# Redundant_Batteries.net
KiCad netlist of a schematic drawn in Altium Designer
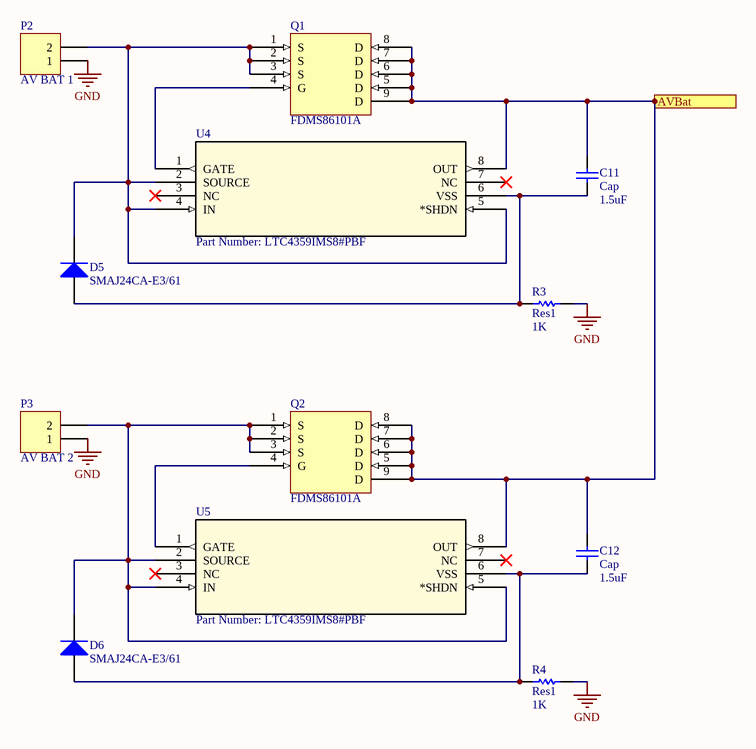
[diagram p0: Redundant Batteries.SchDoc]

(export (version "E")
  (design (tool "Eeschema 10.0.6"))
  (components
    (comp (ref "C11")
      (value "Cap")
      (footprint "CAP_2012")
      (description "Capacitor")
      (fields (field (name "ALTIUM_VALUE") "1.5uF") (field (name "PUBLISHER") "Altium Limited"))
      (libsource (lib "Miscellaneous Devices") (part "Cap"))
    )
    (comp (ref "C12")
      (value "Cap")
      (footprint "CAP_2012")
      (description "Capacitor")
      (fields (field (name "ALTIUM_VALUE") "1.5uF") (field (name "PUBLISHER") "Altium Limited"))
      (libsource (lib "Miscellaneous Devices") (part "Cap"))
    )
    (comp (ref "D5")
      (value "SMAJ24CA-E3/61")
      (footprint "DIODE_DO-214AC")
      (description "Default Diode")
      (fields (field (name "PUBLISHER") "Altium Limited"))
      (libsource (lib "Miscellaneous Devices") (part "Diode"))
    )
    (comp (ref "D6")
      (value "SMAJ24CA-E3/61")
      (footprint "DIODE_DO-214AC")
      (description "Default Diode")
      (fields (field (name "PUBLISHER") "Altium Limited"))
      (libsource (lib "Miscellaneous Devices") (part "Diode"))
    )
    (comp (ref "P2")
      (value "AV BAT 1")
      (footprint "M80-5000000M5-02-333-00-000")
      (description "Header, 2-Pin")
      (fields (field (name "PUBLISHER") "Altium Limited"))
      (libsource (lib "Miscellaneous Connectors") (part "Header 2"))
    )
    (comp (ref "P3")
      (value "AV BAT 2")
      (footprint "M80-5000000M5-02-333-00-000")
      (description "Header, 2-Pin")
      (fields (field (name "PUBLISHER") "Altium Limited"))
      (libsource (lib "Miscellaneous Connectors") (part "Header 2"))
    )
    (comp (ref "Q1")
      (value "FDMS86101A")
      (footprint "FDMS86101A")
      (description "MOSFET N-CH 100V 13A POWER56")
      (libsource (lib "FDMS86101A") (part "FDMS86101A"))
    )
    (comp (ref "Q2")
      (value "FDMS86101A")
      (footprint "FDMS86101A")
      (description "MOSFET N-CH 100V 13A POWER56")
      (libsource (lib "FDMS86101A") (part "FDMS86101A"))
    )
    (comp (ref "R3")
      (value "Res1")
      (footprint "STA_RMCF2512")
      (description "Resistor")
      (fields (field (name "ALTIUM_VALUE") "1K") (field (name "PUBLISHER") "Altium Limited"))
      (libsource (lib "Miscellaneous Devices") (part "Res1"))
    )
    (comp (ref "R4")
      (value "Res1")
      (footprint "STA_RMCF2512")
      (description "Resistor")
      (fields (field (name "ALTIUM_VALUE") "1K") (field (name "PUBLISHER") "Altium Limited"))
      (libsource (lib "Miscellaneous Devices") (part "Res1"))
    )
    (comp (ref "U4")
      (value "Part Number: LTC4359IMS8#PBF")
      (footprint "MSOP-8_MS")
      (description "No Description Available")
      (fields
        (field (name "MANUFACTURER_PART_NUMBER") "LTC4359IMS8#PBF")
        (field (name "COPYRIGHT") "Copyright (C) 2018 Accelerated Designs. All rights reserved")
      )
      (libsource (lib "LTC4359IMS8#PBF") (part "LTC4359IMS8#PBF"))
    )
    (comp (ref "U5")
      (value "Part Number: LTC4359IMS8#PBF")
      (footprint "MSOP-8_MS")
      (description "No Description Available")
      (fields
        (field (name "MANUFACTURER_PART_NUMBER") "LTC4359IMS8#PBF")
        (field (name "COPYRIGHT") "Copyright (C) 2018 Accelerated Designs. All rights reserved")
      )
      (libsource (lib "LTC4359IMS8#PBF") (part "LTC4359IMS8#PBF"))
    )
  )
  (nets
    (net (code "1") (name "/AVBat") (class "Default")
      (node (ref "C11") (pin "2") (pinfunction "2_2") (pintype "passive"))
      (node (ref "C12") (pin "2") (pinfunction "2_2") (pintype "passive"))
      (node (ref "Q1") (pin "5") (pinfunction "D_5") (pintype "input"))
      (node (ref "Q1") (pin "6") (pinfunction "D_6") (pintype "input"))
      (node (ref "Q1") (pin "7") (pinfunction "D_7") (pintype "input"))
      (node (ref "Q1") (pin "8") (pinfunction "D_8") (pintype "input"))
      (node (ref "Q1") (pin "9") (pinfunction "D_9") (pintype "passive"))
      (node (ref "Q2") (pin "5") (pinfunction "D_5") (pintype "input"))
      (node (ref "Q2") (pin "6") (pinfunction "D_6") (pintype "input"))
      (node (ref "Q2") (pin "7") (pinfunction "D_7") (pintype "input"))
      (node (ref "Q2") (pin "8") (pinfunction "D_8") (pintype "input"))
      (node (ref "Q2") (pin "9") (pinfunction "D_9") (pintype "passive"))
      (node (ref "U4") (pin "8") (pinfunction "OUT_8") (pintype "output"))
      (node (ref "U5") (pin "8") (pinfunction "OUT_8") (pintype "output"))
    )
    (net (code "2") (name "GND") (class "Default")
      (node (ref "P2") (pin "1") (pinfunction "1_1") (pintype "passive"))
      (node (ref "P3") (pin "1") (pinfunction "1_1") (pintype "passive"))
      (node (ref "R3") (pin "2") (pinfunction "2_2") (pintype "passive"))
      (node (ref "R4") (pin "2") (pinfunction "2_2") (pintype "passive"))
    )
    (net (code "3") (name "Net-(D5-A)") (class "Default")
      (node (ref "C11") (pin "1") (pinfunction "1_1") (pintype "passive"))
      (node (ref "D5") (pin "1") (pinfunction "A_1") (pintype "passive"))
      (node (ref "R3") (pin "1") (pinfunction "1_1") (pintype "passive"))
      (node (ref "U4") (pin "6") (pinfunction "VSS_6") (pintype "power_in"))
    )
    (net (code "4") (name "Net-(D5-K)") (class "Default")
      (node (ref "D5") (pin "2") (pinfunction "K_2") (pintype "passive"))
      (node (ref "P2") (pin "2") (pinfunction "2_2") (pintype "passive"))
      (node (ref "Q1") (pin "1") (pinfunction "S_1") (pintype "input"))
      (node (ref "Q1") (pin "2") (pinfunction "S_2") (pintype "input"))
      (node (ref "Q1") (pin "3") (pinfunction "S_3") (pintype "input"))
      (node (ref "U4") (pin "2") (pinfunction "SOURCE_2") (pintype "passive"))
      (node (ref "U4") (pin "4") (pinfunction "IN_4") (pintype "input"))
      (node (ref "U4") (pin "5") (pinfunction "*SHDN_5") (pintype "input"))
    )
    (net (code "5") (name "Net-(D6-A)") (class "Default")
      (node (ref "C12") (pin "1") (pinfunction "1_1") (pintype "passive"))
      (node (ref "D6") (pin "1") (pinfunction "A_1") (pintype "passive"))
      (node (ref "R4") (pin "1") (pinfunction "1_1") (pintype "passive"))
      (node (ref "U5") (pin "6") (pinfunction "VSS_6") (pintype "power_in"))
    )
    (net (code "6") (name "Net-(D6-K)") (class "Default")
      (node (ref "D6") (pin "2") (pinfunction "K_2") (pintype "passive"))
      (node (ref "P3") (pin "2") (pinfunction "2_2") (pintype "passive"))
      (node (ref "Q2") (pin "1") (pinfunction "S_1") (pintype "input"))
      (node (ref "Q2") (pin "2") (pinfunction "S_2") (pintype "input"))
      (node (ref "Q2") (pin "3") (pinfunction "S_3") (pintype "input"))
      (node (ref "U5") (pin "2") (pinfunction "SOURCE_2") (pintype "passive"))
      (node (ref "U5") (pin "4") (pinfunction "IN_4") (pintype "input"))
      (node (ref "U5") (pin "5") (pinfunction "*SHDN_5") (pintype "input"))
    )
    (net (code "7") (name "Net-(Q1-G)") (class "Default")
      (node (ref "Q1") (pin "4") (pinfunction "G_4") (pintype "input"))
      (node (ref "U4") (pin "1") (pinfunction "GATE_1") (pintype "output"))
    )
    (net (code "8") (name "Net-(Q2-G)") (class "Default")
      (node (ref "Q2") (pin "4") (pinfunction "G_4") (pintype "input"))
      (node (ref "U5") (pin "1") (pinfunction "GATE_1") (pintype "output"))
    )
    (net (code "9") (name "unconnected-(U4-NC-Pad3)") (class "Default")
      (node (ref "U4") (pin "3") (pinfunction "NC_3") (pintype "passive+no_connect"))
    )
    (net (code "10") (name "unconnected-(U4-NC-Pad7)") (class "Default")
      (node (ref "U4") (pin "7") (pinfunction "NC_7") (pintype "passive+no_connect"))
    )
    (net (code "11") (name "unconnected-(U5-NC-Pad3)") (class "Default")
      (node (ref "U5") (pin "3") (pinfunction "NC_3") (pintype "passive+no_connect"))
    )
    (net (code "12") (name "unconnected-(U5-NC-Pad7)") (class "Default")
      (node (ref "U5") (pin "7") (pinfunction "NC_7") (pintype "passive+no_connect"))
    )
  )
)
